# v1_USB_UART.net
KiCad netlist of a schematic drawn in EAGLE
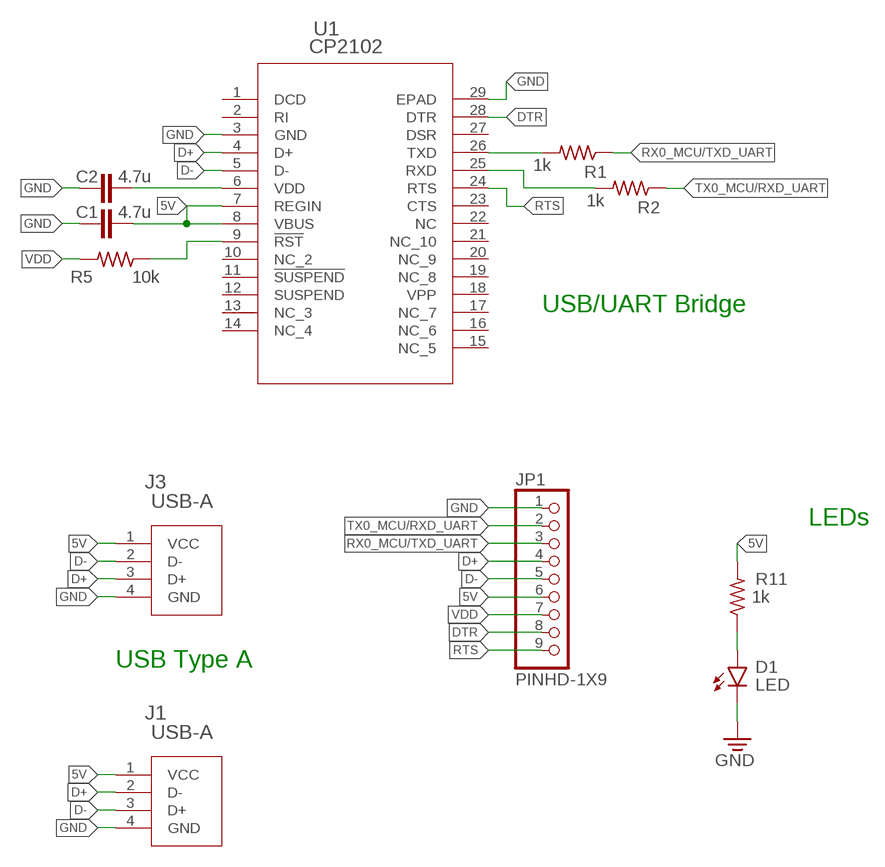
[diagram p0: schematic, sheet 1]

(export (version "E")
  (design (tool "Eeschema 10.0.6"))
  (components
    (comp (ref "C1")
      (value "4.7u")
      (footprint "eagle-import:CAPC2012X110")
      (libsource (lib "eagle-import") (part "CCHIP-0805(2012-METRIC)_"))
    )
    (comp (ref "C2")
      (value "4.7u")
      (footprint "eagle-import:CAPC2012X110")
      (libsource (lib "eagle-import") (part "CCHIP-0805(2012-METRIC)_"))
    )
    (comp (ref "D1")
      (value "LED")
      (footprint "eagle-import:LEDC2012X110N_FLAT-B")
      (libsource (lib "eagle-import") (part "CHIP-FLAT-B_0805"))
    )
    (comp (ref "J1")
      (value "USB-A")
      (footprint "eagle-import:USB-A")
      (fields
        (field (name "MANUFACTURER_PART_NUMBER") "USB-A1VSB6")
        (field (name "COPYRIGHT") "Copyright (C) 2025 Ultra Librarian. All rights reserved.")
      )
      (libsource (lib "eagle-import") (part "USB-A1VSB6_OST"))
    )
    (comp (ref "J3")
      (value "USB-A")
      (footprint "eagle-import:USB-A")
      (fields
        (field (name "MANUFACTURER_PART_NUMBER") "USB-A1VSB6")
        (field (name "COPYRIGHT") "Copyright (C) 2025 Ultra Librarian. All rights reserved.")
      )
      (libsource (lib "eagle-import") (part "USB-A1VSB6_OST"))
    )
    (comp (ref "JP1")
      (value "PINHD-1X9")
      (footprint "eagle-import:1X09")
      (libsource (lib "eagle-import") (part "PINHD-1X9"))
    )
    (comp (ref "R1")
      (value "1k")
      (footprint "eagle-import:RESC2012X65")
      (libsource (lib "eagle-import") (part "R-USCHIP-0805(2012-METRIC)_"))
    )
    (comp (ref "R2")
      (value "1k")
      (footprint "eagle-import:RESC2012X65")
      (libsource (lib "eagle-import") (part "R-USCHIP-0805(2012-METRIC)_"))
    )
    (comp (ref "R5")
      (value "10k")
      (footprint "eagle-import:RESC2012X65")
      (libsource (lib "eagle-import") (part "R-USCHIP-0805(2012-METRIC)_"))
    )
    (comp (ref "R11")
      (value "1k")
      (footprint "eagle-import:RESC2012X65")
      (libsource (lib "eagle-import") (part "R-USCHIP-0805(2012-METRIC)_"))
    )
    (comp (ref "U1")
      (value "CP2102")
      (footprint "eagle-import:QFN28_5X5_SIL")
      (fields
        (field (name "MANUFACTURER_PART_NUMBER") "CP2102-GM")
        (field (name "COPYRIGHT") "Copyright (C) 2025 Ultra Librarian. All rights reserved.")
      )
      (libsource (lib "eagle-import") (part "CP2102-GMQFN28_5X5_SIL"))
    )
  )
  (nets
    (net (code "1") (name "5V") (class "Default")
      (node (ref "C1") (pin "2") (pinfunction "2_2") (pintype "passive"))
      (node (ref "J1") (pin "1") (pinfunction "VCC_1") (pintype "passive"))
      (node (ref "J3") (pin "1") (pinfunction "VCC_1") (pintype "passive"))
      (node (ref "JP1") (pin "6") (pinfunction "6_6") (pintype "passive"))
      (node (ref "R11") (pin "2") (pinfunction "2_2") (pintype "passive"))
      (node (ref "U1") (pin "7") (pinfunction "REGIN_7") (pintype "input"))
      (node (ref "U1") (pin "8") (pinfunction "VBUS_8") (pintype "input"))
    )
    (net (code "2") (name "D+") (class "Default")
      (node (ref "J1") (pin "2") (pinfunction "D-_2") (pintype "passive"))
      (node (ref "J3") (pin "3") (pinfunction "D+_3") (pintype "passive"))
      (node (ref "JP1") (pin "4") (pinfunction "4_4") (pintype "passive"))
      (node (ref "U1") (pin "4") (pinfunction "D+_4") (pintype "bidirectional"))
    )
    (net (code "3") (name "D-") (class "Default")
      (node (ref "J1") (pin "3") (pinfunction "D+_3") (pintype "passive"))
      (node (ref "J3") (pin "2") (pinfunction "D-_2") (pintype "passive"))
      (node (ref "JP1") (pin "5") (pinfunction "5_5") (pintype "passive"))
      (node (ref "U1") (pin "5") (pinfunction "D-_5") (pintype "bidirectional"))
    )
    (net (code "4") (name "DTR") (class "Default")
      (node (ref "JP1") (pin "8") (pinfunction "8_8") (pintype "passive"))
      (node (ref "U1") (pin "28") (pinfunction "DTR_28") (pintype "output"))
    )
    (net (code "5") (name "GND") (class "Default")
      (node (ref "C1") (pin "1") (pinfunction "1_1") (pintype "passive"))
      (node (ref "C2") (pin "1") (pinfunction "1_1") (pintype "passive"))
      (node (ref "D1") (pin "C") (pinfunction "C_C") (pintype "passive"))
      (node (ref "J1") (pin "4") (pinfunction "GND_4") (pintype "passive"))
      (node (ref "J3") (pin "4") (pinfunction "GND_4") (pintype "passive"))
      (node (ref "JP1") (pin "1") (pinfunction "1_1") (pintype "passive"))
      (node (ref "U1") (pin "29") (pinfunction "EPAD_29") (pintype "passive"))
      (node (ref "U1") (pin "3") (pinfunction "GND_3") (pintype "power_in"))
    )
    (net (code "6") (name "Net-(D1-PadA)") (class "Default")
      (node (ref "D1") (pin "A") (pinfunction "A_A") (pintype "passive"))
      (node (ref "R11") (pin "1") (pinfunction "1_1") (pintype "passive"))
    )
    (net (code "7") (name "Net-(U1-RXD)") (class "Default")
      (node (ref "R2") (pin "2") (pinfunction "2_2") (pintype "passive"))
      (node (ref "U1") (pin "25") (pinfunction "RXD_25") (pintype "input"))
    )
    (net (code "8") (name "Net-(U1-TXD)") (class "Default")
      (node (ref "R1") (pin "2") (pinfunction "2_2") (pintype "passive"))
      (node (ref "U1") (pin "26") (pinfunction "TXD_26") (pintype "output"))
    )
    (net (code "9") (name "Net-(U1-~{RST})") (class "Default")
      (node (ref "R5") (pin "1") (pinfunction "1_1") (pintype "passive"))
      (node (ref "U1") (pin "9") (pinfunction "~{RST}_9") (pintype "bidirectional"))
    )
    (net (code "10") (name "RTS") (class "Default")
      (node (ref "JP1") (pin "9") (pinfunction "9_9") (pintype "passive"))
      (node (ref "U1") (pin "24") (pinfunction "RTS_24") (pintype "output"))
    )
    (net (code "11") (name "RX0_MCU{slash}TXD_UART") (class "Default")
      (node (ref "JP1") (pin "3") (pinfunction "3_3") (pintype "passive"))
      (node (ref "R1") (pin "1") (pinfunction "1_1") (pintype "passive"))
    )
    (net (code "12") (name "TX0_MCU{slash}RXD_UART") (class "Default")
      (node (ref "JP1") (pin "2") (pinfunction "2_2") (pintype "passive"))
      (node (ref "R2") (pin "1") (pinfunction "1_1") (pintype "passive"))
    )
    (net (code "13") (name "VDD") (class "Default")
      (node (ref "C2") (pin "2") (pinfunction "2_2") (pintype "passive"))
      (node (ref "JP1") (pin "7") (pinfunction "7_7") (pintype "passive"))
      (node (ref "R5") (pin "2") (pinfunction "2_2") (pintype "passive"))
      (node (ref "U1") (pin "6") (pinfunction "VDD_6") (pintype "power_in"))
    )
    (net (code "14") (name "unconnected-(U1-CTS-Pad23)") (class "Default")
      (node (ref "U1") (pin "23") (pinfunction "CTS_23") (pintype "no_connect"))
    )
    (net (code "15") (name "unconnected-(U1-DCD-Pad1)") (class "Default")
      (node (ref "U1") (pin "1") (pinfunction "DCD_1") (pintype "no_connect"))
    )
    (net (code "16") (name "unconnected-(U1-DSR-Pad27)") (class "Default")
      (node (ref "U1") (pin "27") (pinfunction "DSR_27") (pintype "no_connect"))
    )
    (net (code "17") (name "unconnected-(U1-NC-Pad22)") (class "Default")
      (node (ref "U1") (pin "22") (pinfunction "NC_22") (pintype "no_connect"))
    )
    (net (code "18") (name "unconnected-(U1-NC_2-Pad10)") (class "Default")
      (node (ref "U1") (pin "10") (pinfunction "NC_2_10") (pintype "no_connect"))
    )
    (net (code "19") (name "unconnected-(U1-NC_3-Pad13)") (class "Default")
      (node (ref "U1") (pin "13") (pinfunction "NC_3_13") (pintype "no_connect"))
    )
    (net (code "20") (name "unconnected-(U1-NC_4-Pad14)") (class "Default")
      (node (ref "U1") (pin "14") (pinfunction "NC_4_14") (pintype "no_connect"))
    )
    (net (code "21") (name "unconnected-(U1-NC_5-Pad15)") (class "Default")
      (node (ref "U1") (pin "15") (pinfunction "NC_5_15") (pintype "no_connect"))
    )
    (net (code "22") (name "unconnected-(U1-NC_6-Pad16)") (class "Default")
      (node (ref "U1") (pin "16") (pinfunction "NC_6_16") (pintype "no_connect"))
    )
    (net (code "23") (name "unconnected-(U1-NC_7-Pad17)") (class "Default")
      (node (ref "U1") (pin "17") (pinfunction "NC_7_17") (pintype "no_connect"))
    )
    (net (code "24") (name "unconnected-(U1-NC_8-Pad19)") (class "Default")
      (node (ref "U1") (pin "19") (pinfunction "NC_8_19") (pintype "no_connect"))
    )
    (net (code "25") (name "unconnected-(U1-NC_9-Pad20)") (class "Default")
      (node (ref "U1") (pin "20") (pinfunction "NC_9_20") (pintype "no_connect"))
    )
    (net (code "26") (name "unconnected-(U1-NC_10-Pad21)") (class "Default")
      (node (ref "U1") (pin "21") (pinfunction "NC_10_21") (pintype "no_connect"))
    )
    (net (code "27") (name "unconnected-(U1-RI-Pad2)") (class "Default")
      (node (ref "U1") (pin "2") (pinfunction "RI_2") (pintype "no_connect"))
    )
    (net (code "28") (name "unconnected-(U1-SUSPEND-Pad12)") (class "Default")
      (node (ref "U1") (pin "12") (pinfunction "SUSPEND_12") (pintype "no_connect"))
    )
    (net (code "29") (name "unconnected-(U1-VPP-Pad18)") (class "Default")
      (node (ref "U1") (pin "18") (pinfunction "VPP_18") (pintype "no_connect"))
    )
    (net (code "30") (name "unconnected-(U1-~{SUSPEND}-Pad11)") (class "Default")
      (node (ref "U1") (pin "11") (pinfunction "~{SUSPEND}_11") (pintype "no_connect"))
    )
  )
)
